# bat_connectors.net
KiCad netlist of a schematic drawn in Altium Designer
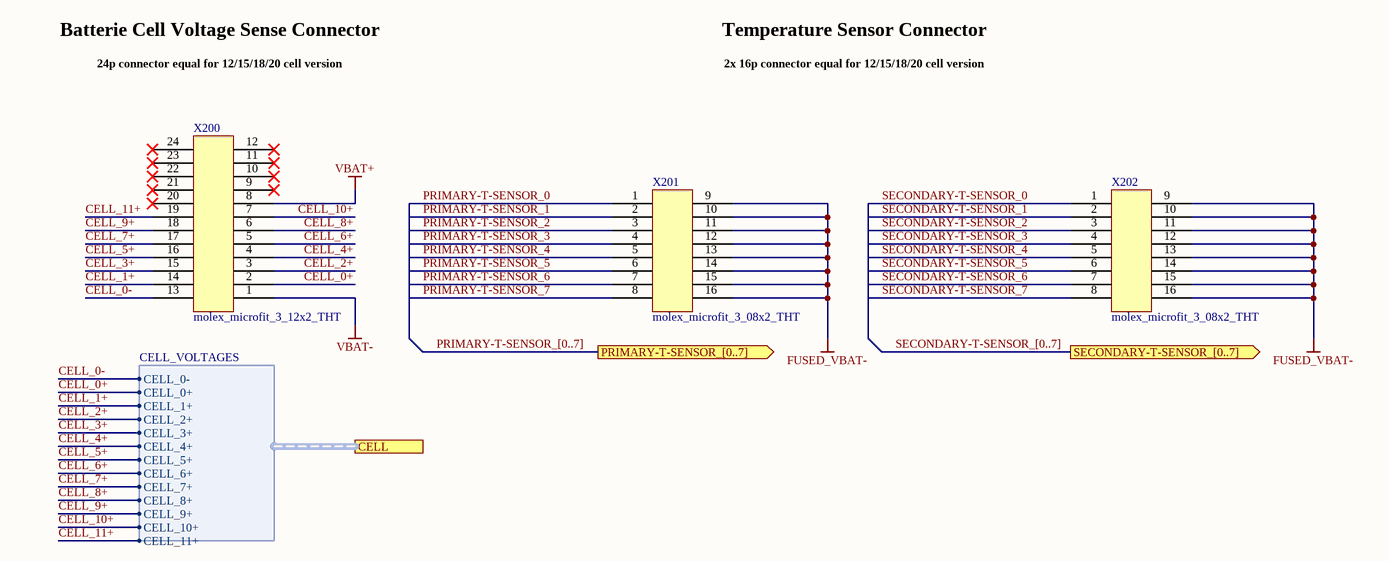
[diagram p0: bat_connectors.SchDoc]

(export (version "E")
  (design (tool "Eeschema 10.0.6"))
  (components
    (comp (ref "X200")
      (value "molex_microfit_3_12x2_THT")
      (footprint "MOLEX_MICROFIT_12x2_THT")
      (fields (field (name "MANUFACTURER") "Molex"))
      (libsource (lib "OE750") (part "X12x2"))
    )
    (comp (ref "X201")
      (value "molex_microfit_3_08x2_THT")
      (footprint "MOLEX_MICROFIT_08x2_THT")
      (fields (field (name "MANUFACTURER") "Molex"))
      (libsource (lib "OE750") (part "X8x2"))
    )
    (comp (ref "X202")
      (value "molex_microfit_3_08x2_THT")
      (footprint "MOLEX_MICROFIT_08x2_THT")
      (fields (field (name "MANUFACTURER") "Molex"))
      (libsource (lib "OE750") (part "X8x2"))
    )
  )
  (nets
    (net (code "2") (name "/CELL_0+") (class "Default") (node (ref "X200") (pin "2") (pintype "passive")))
    (net (code "3") (name "/CELL_0-") (class "Default") (node (ref "X200") (pin "13") (pintype "passive")))
    (net (code "4") (name "/CELL_1+") (class "Default") (node (ref "X200") (pin "14") (pintype "passive")))
    (net (code "5") (name "/CELL_2+") (class "Default") (node (ref "X200") (pin "3") (pintype "passive")))
    (net (code "6") (name "/CELL_3+") (class "Default") (node (ref "X200") (pin "15") (pintype "passive")))
    (net (code "7") (name "/CELL_4+") (class "Default") (node (ref "X200") (pin "4") (pintype "passive")))
    (net (code "8") (name "/CELL_5+") (class "Default") (node (ref "X200") (pin "16") (pintype "passive")))
    (net (code "9") (name "/CELL_6+") (class "Default") (node (ref "X200") (pin "5") (pintype "passive")))
    (net (code "10") (name "/CELL_7+") (class "Default") (node (ref "X200") (pin "17") (pintype "passive")))
    (net (code "11") (name "/CELL_8+") (class "Default") (node (ref "X200") (pin "6") (pintype "passive")))
    (net (code "12") (name "/CELL_9+") (class "Default") (node (ref "X200") (pin "18") (pintype "passive")))
    (net (code "13") (name "/CELL_10+") (class "Default") (node (ref "X200") (pin "7") (pintype "passive")))
    (net (code "14") (name "/CELL_11+") (class "Default") (node (ref "X200") (pin "19") (pintype "passive")))
    (net (code "15") (name "/PRIMARY-T-SENSOR_0") (class "Default")
      (node (ref "X201") (pin "1") (pintype "passive"))
    )
    (net (code "16") (name "/PRIMARY-T-SENSOR_1") (class "Default")
      (node (ref "X201") (pin "2") (pintype "passive"))
    )
    (net (code "17") (name "/PRIMARY-T-SENSOR_2") (class "Default")
      (node (ref "X201") (pin "3") (pintype "passive"))
    )
    (net (code "18") (name "/PRIMARY-T-SENSOR_3") (class "Default")
      (node (ref "X201") (pin "4") (pintype "passive"))
    )
    (net (code "19") (name "/PRIMARY-T-SENSOR_4") (class "Default")
      (node (ref "X201") (pin "5") (pintype "passive"))
    )
    (net (code "20") (name "/PRIMARY-T-SENSOR_5") (class "Default")
      (node (ref "X201") (pin "6") (pintype "passive"))
    )
    (net (code "21") (name "/PRIMARY-T-SENSOR_6") (class "Default")
      (node (ref "X201") (pin "7") (pintype "passive"))
    )
    (net (code "22") (name "/PRIMARY-T-SENSOR_7") (class "Default")
      (node (ref "X201") (pin "8") (pintype "passive"))
    )
    (net (code "24") (name "/SECONDARY-T-SENSOR_0") (class "Default")
      (node (ref "X202") (pin "1") (pintype "passive"))
    )
    (net (code "25") (name "/SECONDARY-T-SENSOR_1") (class "Default")
      (node (ref "X202") (pin "2") (pintype "passive"))
    )
    (net (code "26") (name "/SECONDARY-T-SENSOR_2") (class "Default")
      (node (ref "X202") (pin "3") (pintype "passive"))
    )
    (net (code "27") (name "/SECONDARY-T-SENSOR_3") (class "Default")
      (node (ref "X202") (pin "4") (pintype "passive"))
    )
    (net (code "28") (name "/SECONDARY-T-SENSOR_4") (class "Default")
      (node (ref "X202") (pin "5") (pintype "passive"))
    )
    (net (code "29") (name "/SECONDARY-T-SENSOR_5") (class "Default")
      (node (ref "X202") (pin "6") (pintype "passive"))
    )
    (net (code "30") (name "/SECONDARY-T-SENSOR_6") (class "Default")
      (node (ref "X202") (pin "7") (pintype "passive"))
    )
    (net (code "31") (name "/SECONDARY-T-SENSOR_7") (class "Default")
      (node (ref "X202") (pin "8") (pintype "passive"))
    )
    (net (code "34") (name "FUSED_VBAT-") (class "Default")
      (node (ref "X201") (pin "10") (pintype "passive"))
      (node (ref "X201") (pin "11") (pintype "passive"))
      (node (ref "X201") (pin "12") (pintype "passive"))
      (node (ref "X201") (pin "13") (pintype "passive"))
      (node (ref "X201") (pin "14") (pintype "passive"))
      (node (ref "X201") (pin "15") (pintype "passive"))
      (node (ref "X201") (pin "16") (pintype "passive"))
      (node (ref "X201") (pin "9") (pintype "passive"))
      (node (ref "X202") (pin "10") (pintype "passive"))
      (node (ref "X202") (pin "11") (pintype "passive"))
      (node (ref "X202") (pin "12") (pintype "passive"))
      (node (ref "X202") (pin "13") (pintype "passive"))
      (node (ref "X202") (pin "14") (pintype "passive"))
      (node (ref "X202") (pin "15") (pintype "passive"))
      (node (ref "X202") (pin "16") (pintype "passive"))
      (node (ref "X202") (pin "9") (pintype "passive"))
    )
    (net (code "35") (name "VBAT+") (class "Default") (node (ref "X200") (pin "8") (pintype "passive")))
    (net (code "36") (name "VBAT-") (class "Default") (node (ref "X200") (pin "1") (pintype "passive")))
    (net (code "37") (name "unconnected-(X200-Pad9)") (class "Default")
      (node (ref "X200") (pin "9") (pintype "passive+no_connect"))
    )
    (net (code "38") (name "unconnected-(X200-Pad10)") (class "Default")
      (node (ref "X200") (pin "10") (pintype "passive+no_connect"))
    )
    (net (code "39") (name "unconnected-(X200-Pad11)") (class "Default")
      (node (ref "X200") (pin "11") (pintype "passive+no_connect"))
    )
    (net (code "40") (name "unconnected-(X200-Pad12)") (class "Default")
      (node (ref "X200") (pin "12") (pintype "passive+no_connect"))
    )
    (net (code "41") (name "unconnected-(X200-Pad20)") (class "Default")
      (node (ref "X200") (pin "20") (pintype "passive+no_connect"))
    )
    (net (code "42") (name "unconnected-(X200-Pad21)") (class "Default")
      (node (ref "X200") (pin "21") (pintype "passive+no_connect"))
    )
    (net (code "43") (name "unconnected-(X200-Pad22)") (class "Default")
      (node (ref "X200") (pin "22") (pintype "passive+no_connect"))
    )
    (net (code "44") (name "unconnected-(X200-Pad23)") (class "Default")
      (node (ref "X200") (pin "23") (pintype "passive+no_connect"))
    )
    (net (code "45") (name "unconnected-(X200-Pad24)") (class "Default")
      (node (ref "X200") (pin "24") (pintype "passive+no_connect"))
    )
  )
)
